# nixie-frontpanel.net
KiCad netlist of a schematic drawn in EAGLE
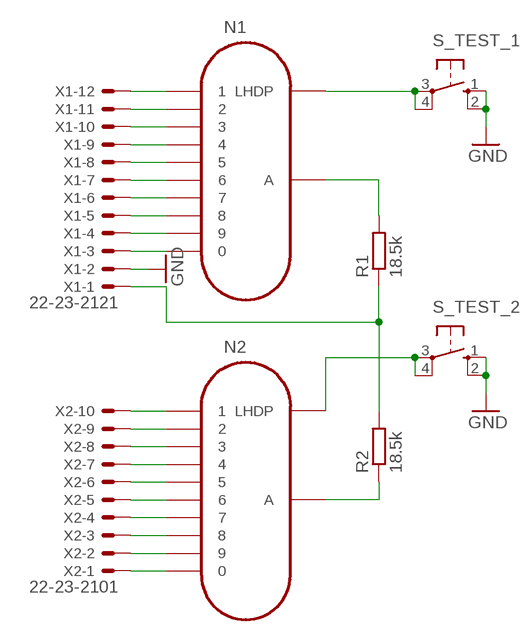
[diagram p0: schematic, sheet 1]

(export (version "E")
  (design (tool "Eeschema 10.0.6"))
  (components
    (comp (ref "N1")
      (value "IN-12B")
      (footprint "eagle-import:IN-12")
      (libsource (lib "eagle-import") (part "IN-12B"))
    )
    (comp (ref "N2")
      (value "IN-12B")
      (footprint "eagle-import:IN-12")
      (libsource (lib "eagle-import") (part "IN-12B"))
    )
    (comp (ref "R1")
      (value "18.5k")
      (footprint "eagle-import:M0805")
      (libsource (lib "eagle-import") (part "R-EU_M0805"))
    )
    (comp (ref "R2")
      (value "18.5k")
      (footprint "eagle-import:M0805")
      (libsource (lib "eagle-import") (part "R-EU_M0805"))
    )
    (comp (ref "S_TEST_1")
      (value "10-XX")
      (footprint "eagle-import:B3F-10XX")
      (fields (field (name "MPN") "B3F-1000"))
      (libsource (lib "eagle-import") (part "10-XX"))
    )
    (comp (ref "S_TEST_2")
      (value "10-XX")
      (footprint "eagle-import:B3F-10XX")
      (fields (field (name "MPN") "B3F-1000"))
      (libsource (lib "eagle-import") (part "10-XX"))
    )
    (comp (ref "X1")
      (value "22-23-2121")
      (footprint "eagle-import:22-23-2121")
      (fields (field (name "MF") "MOLEX"))
      (libsource (lib "eagle-import") (part "22-23-2121"))
    )
    (comp (ref "X2")
      (value "22-23-2101")
      (footprint "eagle-import:22-23-2101")
      (fields (field (name "MF") "MOLEX"))
      (libsource (lib "eagle-import") (part "22-23-2101"))
    )
  )
  (nets
    (net (code "1") (name "GND") (class "Default")
      (node (ref "S_TEST_1") (pin "1") (pinfunction "S_1") (pintype "passive"))
      (node (ref "S_TEST_1") (pin "2") (pinfunction "S1_2") (pintype "passive"))
      (node (ref "S_TEST_2") (pin "1") (pinfunction "S_1") (pintype "passive"))
      (node (ref "S_TEST_2") (pin "2") (pinfunction "S1_2") (pintype "passive"))
      (node (ref "X1") (pin "2") (pinfunction "S_2") (pintype "passive"))
    )
    (net (code "2") (name "Net-(N1-PadA)") (class "Default")
      (node (ref "N1") (pin "A") (pinfunction "A_A") (pintype "bidirectional"))
      (node (ref "R1") (pin "2") (pinfunction "2_2") (pintype "passive"))
    )
    (net (code "3") (name "Net-(N2-PadA)") (class "Default")
      (node (ref "N2") (pin "A") (pinfunction "A_A") (pintype "bidirectional"))
      (node (ref "R2") (pin "1") (pinfunction "1_1") (pintype "passive"))
    )
    (net (code "4") (name "Net-(S_TEST_1-P)") (class "Default")
      (node (ref "N1") (pin "LHDP") (pinfunction "LHDP_LHDP") (pintype "bidirectional"))
      (node (ref "S_TEST_1") (pin "3") (pinfunction "P_3") (pintype "passive"))
      (node (ref "S_TEST_1") (pin "4") (pinfunction "P1_4") (pintype "passive"))
    )
    (net (code "5") (name "Net-(S_TEST_2-P)") (class "Default")
      (node (ref "N2") (pin "LHDP") (pinfunction "LHDP_LHDP") (pintype "bidirectional"))
      (node (ref "S_TEST_2") (pin "3") (pinfunction "P_3") (pintype "passive"))
      (node (ref "S_TEST_2") (pin "4") (pinfunction "P1_4") (pintype "passive"))
    )
    (net (code "6") (name "Net-(X1A-S)") (class "Default")
      (node (ref "R1") (pin "1") (pinfunction "1_1") (pintype "passive"))
      (node (ref "R2") (pin "2") (pinfunction "2_2") (pintype "passive"))
      (node (ref "X1") (pin "1") (pinfunction "S_1") (pintype "passive"))
    )
    (net (code "7") (name "Net-(X1B-S)") (class "Default")
      (node (ref "N1") (pin "3") (pinfunction "3_3") (pintype "bidirectional"))
      (node (ref "X1") (pin "10") (pinfunction "S_10") (pintype "passive"))
    )
    (net (code "8") (name "Net-(X1C-S)") (class "Default")
      (node (ref "N1") (pin "2") (pinfunction "2_2") (pintype "bidirectional"))
      (node (ref "X1") (pin "11") (pinfunction "S_11") (pintype "passive"))
    )
    (net (code "9") (name "Net-(X1D-S)") (class "Default")
      (node (ref "N1") (pin "1") (pinfunction "1_1") (pintype "bidirectional"))
      (node (ref "X1") (pin "12") (pinfunction "S_12") (pintype "passive"))
    )
    (net (code "10") (name "Net-(X1F-S)") (class "Default")
      (node (ref "N1") (pin "0") (pinfunction "0_0") (pintype "bidirectional"))
      (node (ref "X1") (pin "3") (pinfunction "S_3") (pintype "passive"))
    )
    (net (code "11") (name "Net-(X1G-S)") (class "Default")
      (node (ref "N1") (pin "9") (pinfunction "9_9") (pintype "bidirectional"))
      (node (ref "X1") (pin "4") (pinfunction "S_4") (pintype "passive"))
    )
    (net (code "12") (name "Net-(X1H-S)") (class "Default")
      (node (ref "N1") (pin "8") (pinfunction "8_8") (pintype "bidirectional"))
      (node (ref "X1") (pin "5") (pinfunction "S_5") (pintype "passive"))
    )
    (net (code "13") (name "Net-(X1I-S)") (class "Default")
      (node (ref "N1") (pin "7") (pinfunction "7_7") (pintype "bidirectional"))
      (node (ref "X1") (pin "6") (pinfunction "S_6") (pintype "passive"))
    )
    (net (code "14") (name "Net-(X1J-S)") (class "Default")
      (node (ref "N1") (pin "6") (pinfunction "6_6") (pintype "bidirectional"))
      (node (ref "X1") (pin "7") (pinfunction "S_7") (pintype "passive"))
    )
    (net (code "15") (name "Net-(X1K-S)") (class "Default")
      (node (ref "N1") (pin "5") (pinfunction "5_5") (pintype "bidirectional"))
      (node (ref "X1") (pin "8") (pinfunction "S_8") (pintype "passive"))
    )
    (net (code "16") (name "Net-(X1L-S)") (class "Default")
      (node (ref "N1") (pin "4") (pinfunction "4_4") (pintype "bidirectional"))
      (node (ref "X1") (pin "9") (pinfunction "S_9") (pintype "passive"))
    )
    (net (code "17") (name "Net-(X2A-S)") (class "Default")
      (node (ref "N2") (pin "0") (pinfunction "0_0") (pintype "bidirectional"))
      (node (ref "X2") (pin "1") (pinfunction "S_1") (pintype "passive"))
    )
    (net (code "18") (name "Net-(X2B-S)") (class "Default")
      (node (ref "N2") (pin "1") (pinfunction "1_1") (pintype "bidirectional"))
      (node (ref "X2") (pin "10") (pinfunction "S_10") (pintype "passive"))
    )
    (net (code "19") (name "Net-(X2C-S)") (class "Default")
      (node (ref "N2") (pin "9") (pinfunction "9_9") (pintype "bidirectional"))
      (node (ref "X2") (pin "2") (pinfunction "S_2") (pintype "passive"))
    )
    (net (code "20") (name "Net-(X2D-S)") (class "Default")
      (node (ref "N2") (pin "8") (pinfunction "8_8") (pintype "bidirectional"))
      (node (ref "X2") (pin "3") (pinfunction "S_3") (pintype "passive"))
    )
    (net (code "21") (name "Net-(X2E-S)") (class "Default")
      (node (ref "N2") (pin "7") (pinfunction "7_7") (pintype "bidirectional"))
      (node (ref "X2") (pin "4") (pinfunction "S_4") (pintype "passive"))
    )
    (net (code "22") (name "Net-(X2F-S)") (class "Default")
      (node (ref "N2") (pin "6") (pinfunction "6_6") (pintype "bidirectional"))
      (node (ref "X2") (pin "5") (pinfunction "S_5") (pintype "passive"))
    )
    (net (code "23") (name "Net-(X2G-S)") (class "Default")
      (node (ref "N2") (pin "5") (pinfunction "5_5") (pintype "bidirectional"))
      (node (ref "X2") (pin "6") (pinfunction "S_6") (pintype "passive"))
    )
    (net (code "24") (name "Net-(X2H-S)") (class "Default")
      (node (ref "N2") (pin "4") (pinfunction "4_4") (pintype "bidirectional"))
      (node (ref "X2") (pin "7") (pinfunction "S_7") (pintype "passive"))
    )
    (net (code "25") (name "Net-(X2I-S)") (class "Default")
      (node (ref "N2") (pin "3") (pinfunction "3_3") (pintype "bidirectional"))
      (node (ref "X2") (pin "8") (pinfunction "S_8") (pintype "passive"))
    )
    (net (code "26") (name "Net-(X2J-S)") (class "Default")
      (node (ref "N2") (pin "2") (pinfunction "2_2") (pintype "bidirectional"))
      (node (ref "X2") (pin "9") (pinfunction "S_9") (pintype "passive"))
    )
  )
)
